# FPGAPort.net
KiCad netlist of a schematic drawn in Altium Designer
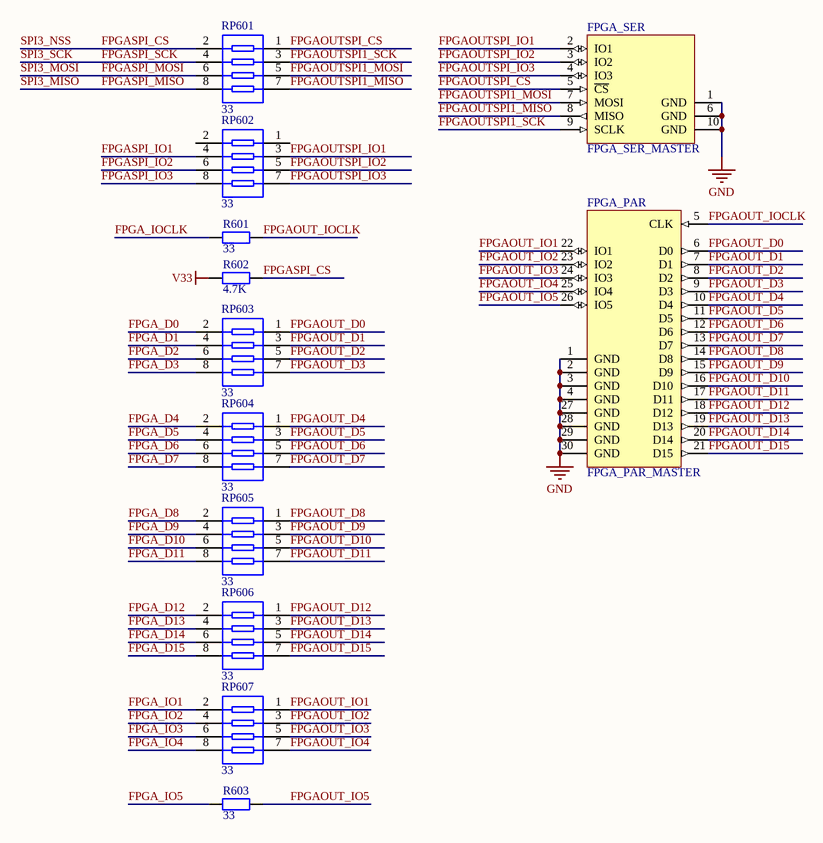
[diagram p0: FPGAPort.SchDoc]

(export (version "E")
  (design (tool "Eeschema 10.0.6"))
  (components
    (comp (ref "FPGA_PAR")
      (value "FPGA_PAR_MASTER")
      (footprint "IDC30")
      (description "FPGA parallel port")
      (libsource (lib "Modules") (part "FPGA_PAR_MASTER"))
    )
    (comp (ref "FPGA_SER")
      (value "FPGA_SER_MASTER")
      (footprint "IDC10")
      (description "FPGA serial port")
      (libsource (lib "Modules") (part "FPGA_SER_MASTER"))
    )
    (comp (ref "R601")
      (value "33")
      (footprint "0603R")
      (description "Resistor")
      (libsource (lib "Misc") (part "Resistor"))
    )
    (comp (ref "R602")
      (value "4.7K")
      (footprint "0603R")
      (description "Resistor")
      (libsource (lib "Misc") (part "Resistor"))
    )
    (comp (ref "R603")
      (value "33")
      (footprint "0603R")
      (description "Resistor")
      (libsource (lib "Misc") (part "Resistor"))
    )
    (comp (ref "RP601")
      (value "33")
      (footprint "8P4R_0603")
      (description "Isolated Resistor Network")
      (fields (field (name "Comment") "Res Pack"))
      (libsource (lib "Misc") (part "Res Pack"))
    )
    (comp (ref "RP602")
      (value "33")
      (footprint "8P4R_0603")
      (description "Isolated Resistor Network")
      (fields (field (name "Comment") "Res Pack"))
      (libsource (lib "Misc") (part "Res Pack"))
    )
    (comp (ref "RP603")
      (value "33")
      (footprint "8P4R_0603")
      (description "Isolated Resistor Network")
      (fields (field (name "Comment") "Res Pack"))
      (libsource (lib "Misc") (part "Res Pack"))
    )
    (comp (ref "RP604")
      (value "33")
      (footprint "8P4R_0603")
      (description "Isolated Resistor Network")
      (fields (field (name "Comment") "Res Pack"))
      (libsource (lib "Misc") (part "Res Pack"))
    )
    (comp (ref "RP605")
      (value "33")
      (footprint "8P4R_0603")
      (description "Isolated Resistor Network")
      (fields (field (name "Comment") "Res Pack"))
      (libsource (lib "Misc") (part "Res Pack"))
    )
    (comp (ref "RP606")
      (value "33")
      (footprint "8P4R_0603")
      (description "Isolated Resistor Network")
      (fields (field (name "Comment") "Res Pack"))
      (libsource (lib "Misc") (part "Res Pack"))
    )
    (comp (ref "RP607")
      (value "33")
      (footprint "8P4R_0603")
      (description "Isolated Resistor Network")
      (fields (field (name "Comment") "Res Pack"))
      (libsource (lib "Misc") (part "Res Pack"))
    )
  )
  (nets
    (net (code "1") (name "/FPGAOUTSPI1_MISO") (class "Default")
      (node (ref "FPGA_SER") (pin "8") (pinfunction "MISO_8") (pintype "output"))
      (node (ref "RP601") (pin "7") (pinfunction "7_7") (pintype "passive"))
    )
    (net (code "2") (name "/FPGAOUTSPI1_MOSI") (class "Default")
      (node (ref "FPGA_SER") (pin "7") (pinfunction "MOSI_7") (pintype "input"))
      (node (ref "RP601") (pin "5") (pinfunction "5_5") (pintype "passive"))
    )
    (net (code "3") (name "/FPGAOUTSPI1_SCK") (class "Default")
      (node (ref "FPGA_SER") (pin "9") (pinfunction "SCLK_9") (pintype "input"))
      (node (ref "RP601") (pin "3") (pinfunction "3_3") (pintype "passive"))
    )
    (net (code "4") (name "/FPGAOUTSPI_CS") (class "Default")
      (node (ref "FPGA_SER") (pin "5") (pinfunction "~{CS}_5") (pintype "input"))
      (node (ref "RP601") (pin "1") (pinfunction "1_1") (pintype "passive"))
    )
    (net (code "5") (name "/FPGAOUTSPI_IO1") (class "Default")
      (node (ref "FPGA_SER") (pin "2") (pinfunction "IO1_2") (pintype "bidirectional"))
      (node (ref "RP602") (pin "3") (pinfunction "3_3") (pintype "passive"))
    )
    (net (code "6") (name "/FPGAOUTSPI_IO2") (class "Default")
      (node (ref "FPGA_SER") (pin "3") (pinfunction "IO2_3") (pintype "bidirectional"))
      (node (ref "RP602") (pin "5") (pinfunction "5_5") (pintype "passive"))
    )
    (net (code "7") (name "/FPGAOUTSPI_IO3") (class "Default")
      (node (ref "FPGA_SER") (pin "4") (pinfunction "IO3_4") (pintype "bidirectional"))
      (node (ref "RP602") (pin "7") (pinfunction "7_7") (pintype "passive"))
    )
    (net (code "8") (name "/FPGAOUT_D0") (class "Default")
      (node (ref "FPGA_PAR") (pin "6") (pinfunction "D0_6") (pintype "output"))
      (node (ref "RP603") (pin "1") (pinfunction "1_1") (pintype "passive"))
    )
    (net (code "9") (name "/FPGAOUT_D1") (class "Default")
      (node (ref "FPGA_PAR") (pin "7") (pinfunction "D1_7") (pintype "output"))
      (node (ref "RP603") (pin "3") (pinfunction "3_3") (pintype "passive"))
    )
    (net (code "10") (name "/FPGAOUT_D2") (class "Default")
      (node (ref "FPGA_PAR") (pin "8") (pinfunction "D2_8") (pintype "output"))
      (node (ref "RP603") (pin "5") (pinfunction "5_5") (pintype "passive"))
    )
    (net (code "11") (name "/FPGAOUT_D3") (class "Default")
      (node (ref "FPGA_PAR") (pin "9") (pinfunction "D3_9") (pintype "output"))
      (node (ref "RP603") (pin "7") (pinfunction "7_7") (pintype "passive"))
    )
    (net (code "12") (name "/FPGAOUT_D4") (class "Default")
      (node (ref "FPGA_PAR") (pin "10") (pinfunction "D4_10") (pintype "output"))
      (node (ref "RP604") (pin "1") (pinfunction "1_1") (pintype "passive"))
    )
    (net (code "13") (name "/FPGAOUT_D5") (class "Default")
      (node (ref "FPGA_PAR") (pin "11") (pinfunction "D5_11") (pintype "output"))
      (node (ref "RP604") (pin "3") (pinfunction "3_3") (pintype "passive"))
    )
    (net (code "14") (name "/FPGAOUT_D6") (class "Default")
      (node (ref "FPGA_PAR") (pin "12") (pinfunction "D6_12") (pintype "output"))
      (node (ref "RP604") (pin "5") (pinfunction "5_5") (pintype "passive"))
    )
    (net (code "15") (name "/FPGAOUT_D7") (class "Default")
      (node (ref "FPGA_PAR") (pin "13") (pinfunction "D7_13") (pintype "output"))
      (node (ref "RP604") (pin "7") (pinfunction "7_7") (pintype "passive"))
    )
    (net (code "16") (name "/FPGAOUT_D8") (class "Default")
      (node (ref "FPGA_PAR") (pin "14") (pinfunction "D8_14") (pintype "output"))
      (node (ref "RP605") (pin "1") (pinfunction "1_1") (pintype "passive"))
    )
    (net (code "17") (name "/FPGAOUT_D9") (class "Default")
      (node (ref "FPGA_PAR") (pin "15") (pinfunction "D9_15") (pintype "output"))
      (node (ref "RP605") (pin "3") (pinfunction "3_3") (pintype "passive"))
    )
    (net (code "18") (name "/FPGAOUT_D10") (class "Default")
      (node (ref "FPGA_PAR") (pin "16") (pinfunction "D10_16") (pintype "output"))
      (node (ref "RP605") (pin "5") (pinfunction "5_5") (pintype "passive"))
    )
    (net (code "19") (name "/FPGAOUT_D11") (class "Default")
      (node (ref "FPGA_PAR") (pin "17") (pinfunction "D11_17") (pintype "output"))
      (node (ref "RP605") (pin "7") (pinfunction "7_7") (pintype "passive"))
    )
    (net (code "20") (name "/FPGAOUT_D12") (class "Default")
      (node (ref "FPGA_PAR") (pin "18") (pinfunction "D12_18") (pintype "output"))
      (node (ref "RP606") (pin "1") (pinfunction "1_1") (pintype "passive"))
    )
    (net (code "21") (name "/FPGAOUT_D13") (class "Default")
      (node (ref "FPGA_PAR") (pin "19") (pinfunction "D13_19") (pintype "output"))
      (node (ref "RP606") (pin "3") (pinfunction "3_3") (pintype "passive"))
    )
    (net (code "22") (name "/FPGAOUT_D14") (class "Default")
      (node (ref "FPGA_PAR") (pin "20") (pinfunction "D14_20") (pintype "output"))
      (node (ref "RP606") (pin "5") (pinfunction "5_5") (pintype "passive"))
    )
    (net (code "23") (name "/FPGAOUT_D15") (class "Default")
      (node (ref "FPGA_PAR") (pin "21") (pinfunction "D15_21") (pintype "output"))
      (node (ref "RP606") (pin "7") (pinfunction "7_7") (pintype "passive"))
    )
    (net (code "24") (name "/FPGAOUT_IO1") (class "Default")
      (node (ref "FPGA_PAR") (pin "22") (pinfunction "IO1_22") (pintype "bidirectional"))
      (node (ref "RP607") (pin "1") (pinfunction "1_1") (pintype "passive"))
    )
    (net (code "25") (name "/FPGAOUT_IO2") (class "Default")
      (node (ref "FPGA_PAR") (pin "23") (pinfunction "IO2_23") (pintype "bidirectional"))
      (node (ref "RP607") (pin "3") (pinfunction "3_3") (pintype "passive"))
    )
    (net (code "26") (name "/FPGAOUT_IO3") (class "Default")
      (node (ref "FPGA_PAR") (pin "24") (pinfunction "IO3_24") (pintype "bidirectional"))
      (node (ref "RP607") (pin "5") (pinfunction "5_5") (pintype "passive"))
    )
    (net (code "27") (name "/FPGAOUT_IO4") (class "Default")
      (node (ref "FPGA_PAR") (pin "25") (pinfunction "IO4_25") (pintype "bidirectional"))
      (node (ref "RP607") (pin "7") (pinfunction "7_7") (pintype "passive"))
    )
    (net (code "28") (name "/FPGAOUT_IO5") (class "Default")
      (node (ref "FPGA_PAR") (pin "26") (pinfunction "IO5_26") (pintype "bidirectional"))
      (node (ref "R603") (pin "2") (pinfunction "2_2") (pintype "passive"))
    )
    (net (code "29") (name "/FPGAOUT_IOCLK") (class "Default")
      (node (ref "FPGA_PAR") (pin "5") (pinfunction "CLK_5") (pintype "input"))
      (node (ref "R601") (pin "2") (pinfunction "2_2") (pintype "passive"))
    )
    (net (code "30") (name "/FPGASPI_CS") (class "Default")
      (node (ref "R602") (pin "2") (pinfunction "2_2") (pintype "passive"))
      (node (ref "RP601") (pin "2") (pinfunction "2_2") (pintype "passive"))
    )
    (net (code "31") (name "/FPGASPI_IO1") (class "Default")
      (node (ref "RP602") (pin "4") (pinfunction "4_4") (pintype "passive"))
    )
    (net (code "32") (name "/FPGASPI_IO2") (class "Default")
      (node (ref "RP602") (pin "6") (pinfunction "6_6") (pintype "passive"))
    )
    (net (code "33") (name "/FPGASPI_IO3") (class "Default")
      (node (ref "RP602") (pin "8") (pinfunction "8_8") (pintype "passive"))
    )
    (net (code "34") (name "/FPGASPI_MISO") (class "Default")
      (node (ref "RP601") (pin "8") (pinfunction "8_8") (pintype "passive"))
    )
    (net (code "35") (name "/FPGASPI_MOSI") (class "Default")
      (node (ref "RP601") (pin "6") (pinfunction "6_6") (pintype "passive"))
    )
    (net (code "36") (name "/FPGASPI_SCK") (class "Default")
      (node (ref "RP601") (pin "4") (pinfunction "4_4") (pintype "passive"))
    )
    (net (code "37") (name "/FPGA_D0") (class "Default")
      (node (ref "RP603") (pin "2") (pinfunction "2_2") (pintype "passive"))
    )
    (net (code "38") (name "/FPGA_D1") (class "Default")
      (node (ref "RP603") (pin "4") (pinfunction "4_4") (pintype "passive"))
    )
    (net (code "39") (name "/FPGA_D2") (class "Default")
      (node (ref "RP603") (pin "6") (pinfunction "6_6") (pintype "passive"))
    )
    (net (code "40") (name "/FPGA_D3") (class "Default")
      (node (ref "RP603") (pin "8") (pinfunction "8_8") (pintype "passive"))
    )
    (net (code "41") (name "/FPGA_D4") (class "Default")
      (node (ref "RP604") (pin "2") (pinfunction "2_2") (pintype "passive"))
    )
    (net (code "42") (name "/FPGA_D5") (class "Default")
      (node (ref "RP604") (pin "4") (pinfunction "4_4") (pintype "passive"))
    )
    (net (code "43") (name "/FPGA_D6") (class "Default")
      (node (ref "RP604") (pin "6") (pinfunction "6_6") (pintype "passive"))
    )
    (net (code "44") (name "/FPGA_D7") (class "Default")
      (node (ref "RP604") (pin "8") (pinfunction "8_8") (pintype "passive"))
    )
    (net (code "45") (name "/FPGA_D8") (class "Default")
      (node (ref "RP605") (pin "2") (pinfunction "2_2") (pintype "passive"))
    )
    (net (code "46") (name "/FPGA_D9") (class "Default")
      (node (ref "RP605") (pin "4") (pinfunction "4_4") (pintype "passive"))
    )
    (net (code "47") (name "/FPGA_D10") (class "Default")
      (node (ref "RP605") (pin "6") (pinfunction "6_6") (pintype "passive"))
    )
    (net (code "48") (name "/FPGA_D11") (class "Default")
      (node (ref "RP605") (pin "8") (pinfunction "8_8") (pintype "passive"))
    )
    (net (code "49") (name "/FPGA_D12") (class "Default")
      (node (ref "RP606") (pin "2") (pinfunction "2_2") (pintype "passive"))
    )
    (net (code "50") (name "/FPGA_D13") (class "Default")
      (node (ref "RP606") (pin "4") (pinfunction "4_4") (pintype "passive"))
    )
    (net (code "51") (name "/FPGA_D14") (class "Default")
      (node (ref "RP606") (pin "6") (pinfunction "6_6") (pintype "passive"))
    )
    (net (code "52") (name "/FPGA_D15") (class "Default")
      (node (ref "RP606") (pin "8") (pinfunction "8_8") (pintype "passive"))
    )
    (net (code "53") (name "/FPGA_IO1") (class "Default")
      (node (ref "RP607") (pin "2") (pinfunction "2_2") (pintype "passive"))
    )
    (net (code "54") (name "/FPGA_IO2") (class "Default")
      (node (ref "RP607") (pin "4") (pinfunction "4_4") (pintype "passive"))
    )
    (net (code "55") (name "/FPGA_IO3") (class "Default")
      (node (ref "RP607") (pin "6") (pinfunction "6_6") (pintype "passive"))
    )
    (net (code "56") (name "/FPGA_IO4") (class "Default")
      (node (ref "RP607") (pin "8") (pinfunction "8_8") (pintype "passive"))
    )
    (net (code "57") (name "/FPGA_IO5") (class "Default")
      (node (ref "R603") (pin "1") (pinfunction "1_1") (pintype "passive"))
    )
    (net (code "58") (name "/FPGA_IOCLK") (class "Default")
      (node (ref "R601") (pin "1") (pinfunction "1_1") (pintype "passive"))
    )
    (net (code "59") (name "GND") (class "Default")
      (node (ref "FPGA_PAR") (pin "1") (pinfunction "GND_1") (pintype "power_in"))
      (node (ref "FPGA_PAR") (pin "2") (pinfunction "GND_2") (pintype "power_in"))
      (node (ref "FPGA_PAR") (pin "27") (pinfunction "GND_27") (pintype "power_in"))
      (node (ref "FPGA_PAR") (pin "28") (pinfunction "GND_28") (pintype "power_in"))
      (node (ref "FPGA_PAR") (pin "29") (pinfunction "GND_29") (pintype "power_in"))
      (node (ref "FPGA_PAR") (pin "3") (pinfunction "GND_3") (pintype "power_in"))
      (node (ref "FPGA_PAR") (pin "30") (pinfunction "GND_30") (pintype "power_in"))
      (node (ref "FPGA_PAR") (pin "4") (pinfunction "GND_4") (pintype "power_in"))
      (node (ref "FPGA_SER") (pin "1") (pinfunction "GND_1") (pintype "power_in"))
      (node (ref "FPGA_SER") (pin "10") (pinfunction "GND_10") (pintype "power_in"))
      (node (ref "FPGA_SER") (pin "6") (pinfunction "GND_6") (pintype "power_in"))
    )
    (net (code "60") (name "V33") (class "Default")
      (node (ref "R602") (pin "1") (pinfunction "1_1") (pintype "passive"))
    )
    (net (code "61") (name "unconnected-(RP602-Pad1)") (class "Default")
      (node (ref "RP602") (pin "1") (pinfunction "1_1") (pintype "passive"))
    )
    (net (code "62") (name "unconnected-(RP602-Pad2)") (class "Default")
      (node (ref "RP602") (pin "2") (pinfunction "2_2") (pintype "passive"))
    )
  )
)
